# ArduSensor_Shield.net
KiCad netlist of a schematic drawn in EAGLE
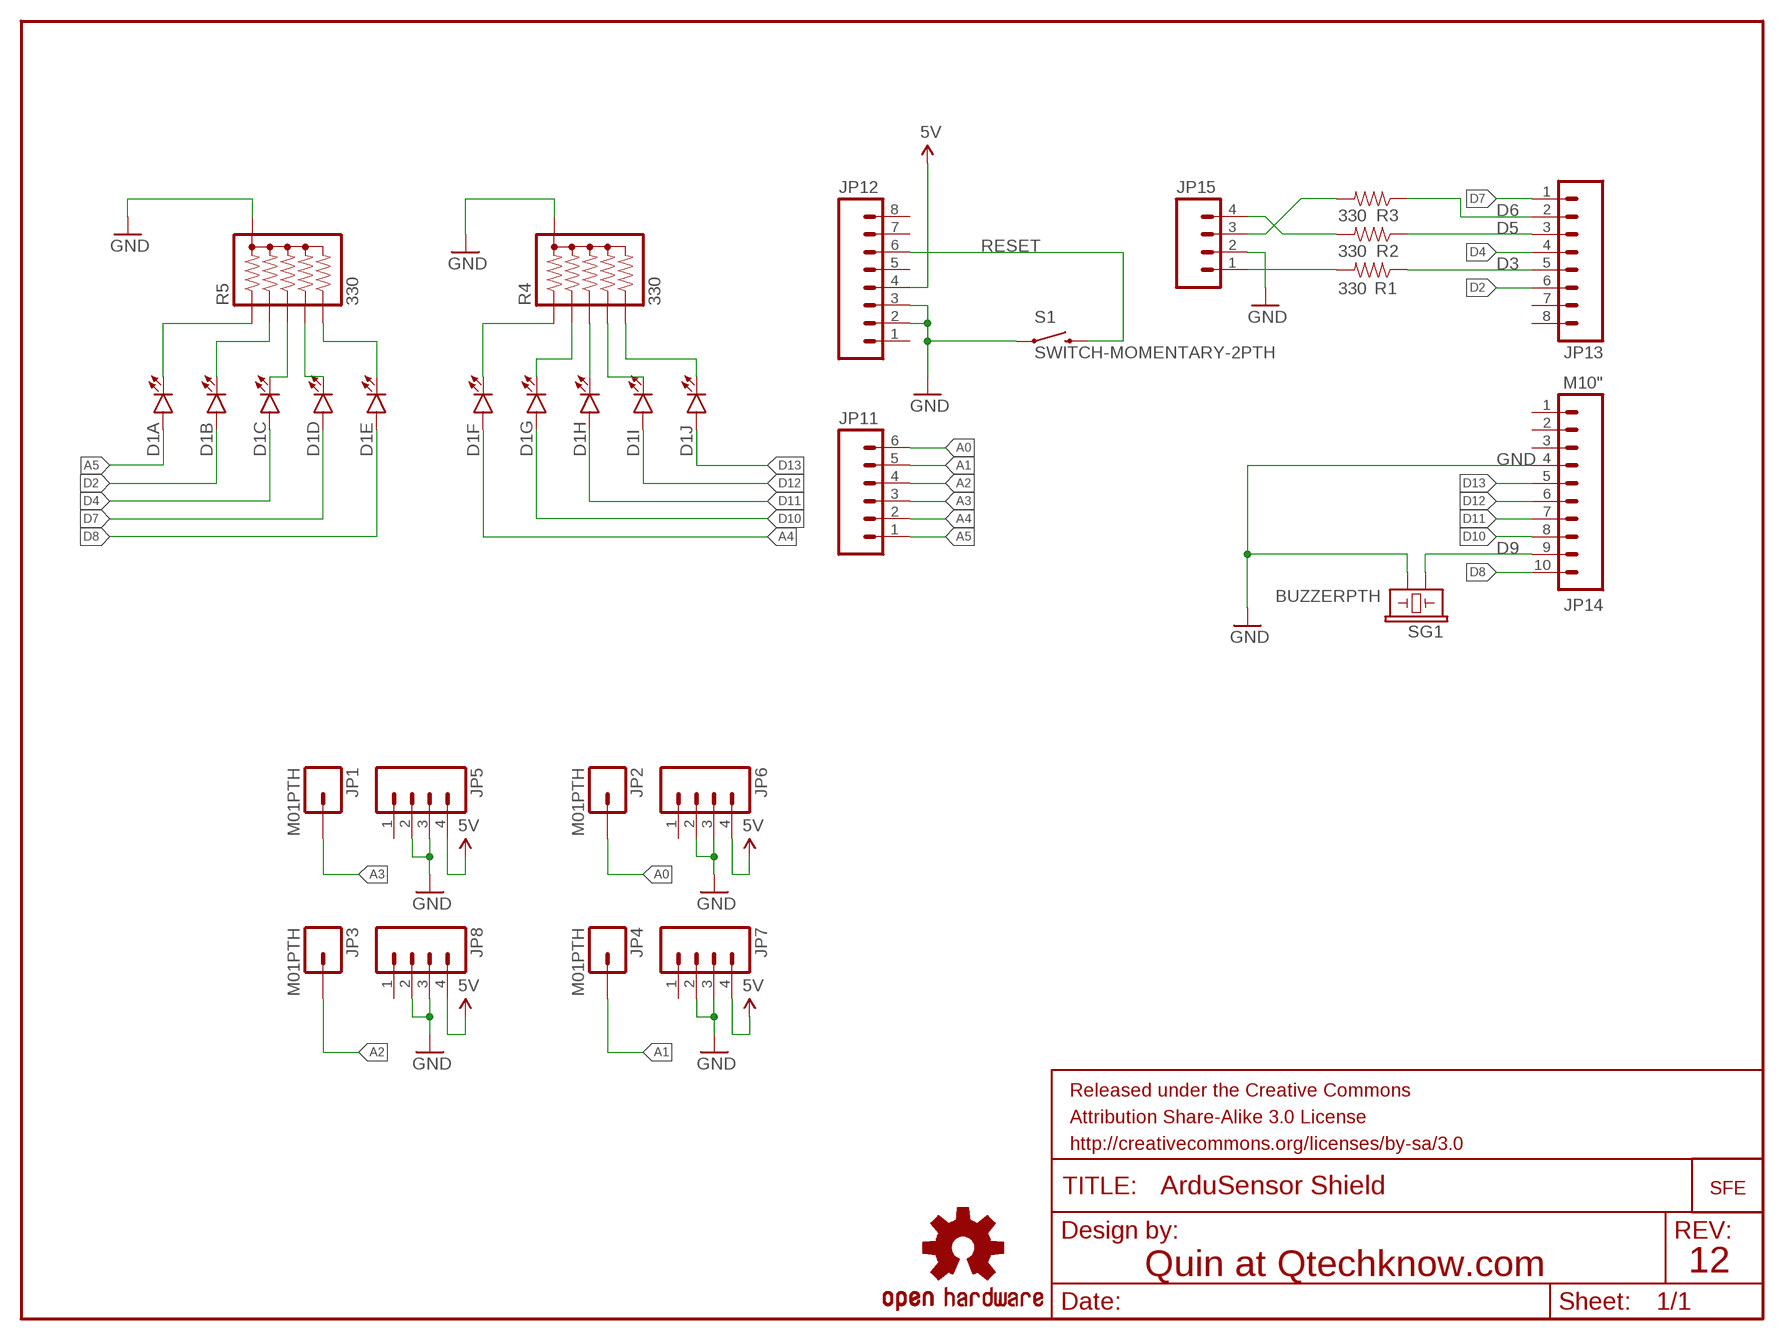
[diagram p0: schematic, sheet 1]

(export (version "E")
  (design (tool "Eeschema 10.0.6"))
  (components
    (comp (ref "D1")
      (value "LED_BARGRAPH_10")
      (footprint "eagle-import:LED_BARGAPH_10")
      (libsource (lib "eagle-import") (part "LED_BARGRAPH_10"))
    )
    (comp (ref "FRAME1")
      (value "FRAME-LETTER")
      (footprint "eagle-import:CREATIVE_COMMONS")
      (libsource (lib "eagle-import") (part "FRAME-LETTER"))
    )
    (comp (ref "JP1")
      (value "M01PTH")
      (footprint "eagle-import:1X01")
      (libsource (lib "eagle-import") (part "M01PTH"))
    )
    (comp (ref "JP2")
      (value "M01PTH")
      (footprint "eagle-import:1X01")
      (libsource (lib "eagle-import") (part "M01PTH"))
    )
    (comp (ref "JP3")
      (value "M01PTH")
      (footprint "eagle-import:1X01")
      (libsource (lib "eagle-import") (part "M01PTH"))
    )
    (comp (ref "JP4")
      (value "M01PTH")
      (footprint "eagle-import:1X01")
      (libsource (lib "eagle-import") (part "M01PTH"))
    )
    (comp (ref "JP5")
      (value "M04PTH")
      (footprint "eagle-import:1X04")
      (libsource (lib "eagle-import") (part "M04PTH"))
    )
    (comp (ref "JP6")
      (value "M04PTH")
      (footprint "eagle-import:1X04")
      (libsource (lib "eagle-import") (part "M04PTH"))
    )
    (comp (ref "JP7")
      (value "M04PTH")
      (footprint "eagle-import:1X04")
      (libsource (lib "eagle-import") (part "M04PTH"))
    )
    (comp (ref "JP8")
      (value "M04PTH")
      (footprint "eagle-import:1X04")
      (libsource (lib "eagle-import") (part "M04PTH"))
    )
    (comp (ref "JP9")
      (value "LOGO-SFENEW")
      (footprint "eagle-import:SFE-NEW-WEBLOGO")
      (libsource (lib "eagle-import") (part "LOGO-SFENEW"))
    )
    (comp (ref "JP11")
      (value "M06SIP")
      (footprint "eagle-import:1X06")
      (libsource (lib "eagle-import") (part "M06SIP"))
    )
    (comp (ref "JP12")
      (value "M081X08")
      (footprint "eagle-import:1X08")
      (libsource (lib "eagle-import") (part "M081X08"))
    )
    (comp (ref "JP13")
      (value "M081X08")
      (footprint "eagle-import:1X08")
      (libsource (lib "eagle-import") (part "M081X08"))
    )
    (comp (ref "JP14")
      (value "M10\"")
      (footprint "eagle-import:1X10")
      (libsource (lib "eagle-import") (part "M10{dblquote}"))
    )
    (comp (ref "JP15")
      (value "M04PTH")
      (footprint "eagle-import:1X04")
      (libsource (lib "eagle-import") (part "M04PTH"))
    )
    (comp (ref "LOGO1")
      (value "OSHW-LOGOM")
      (footprint "eagle-import:OSHW-LOGO-M")
      (libsource (lib "eagle-import") (part "OSHW-LOGOM"))
    )
    (comp (ref "R1")
      (value "330")
      (footprint "eagle-import:1_6W-RES")
      (libsource (lib "eagle-import") (part "RESISTORPTH-1/6W"))
    )
    (comp (ref "R2")
      (value "330")
      (footprint "eagle-import:1_6W-RES")
      (libsource (lib "eagle-import") (part "RESISTORPTH-1/6W"))
    )
    (comp (ref "R3")
      (value "330")
      (footprint "eagle-import:1_6W-RES")
      (libsource (lib "eagle-import") (part "RESISTORPTH-1/6W"))
    )
    (comp (ref "R4")
      (value "330")
      (footprint "eagle-import:RPACK-SIP-PTH-5")
      (libsource (lib "eagle-import") (part "RPACK-BUSSED-SIP-PTH-5"))
    )
    (comp (ref "R5")
      (value "330")
      (footprint "eagle-import:RPACK-SIP-PTH-5")
      (libsource (lib "eagle-import") (part "RPACK-BUSSED-SIP-PTH-5"))
    )
    (comp (ref "S1")
      (value "SWITCH-MOMENTARY-2PTH")
      (footprint "eagle-import:TACTILE-PTH")
      (libsource (lib "eagle-import") (part "SWITCH-MOMENTARY-2PTH"))
    )
    (comp (ref "SG1")
      (value "BUZZERPTH")
      (footprint "eagle-import:BUZZER-12MM")
      (libsource (lib "eagle-import") (part "BUZZERPTH"))
    )
  )
  (nets
    (net (code "1") (name "/D3") (class "Default")
      (node (ref "JP13") (pin "5") (pinfunction "5_5") (pintype "passive"))
      (node (ref "R1") (pin "1") (pinfunction "1_1") (pintype "passive"))
    )
    (net (code "2") (name "/D5") (class "Default")
      (node (ref "JP13") (pin "3") (pinfunction "3_3") (pintype "passive"))
      (node (ref "R2") (pin "1") (pinfunction "1_1") (pintype "passive"))
    )
    (net (code "3") (name "/D6") (class "Default")
      (node (ref "JP13") (pin "2") (pinfunction "2_2") (pintype "passive"))
      (node (ref "R3") (pin "1") (pinfunction "1_1") (pintype "passive"))
    )
    (net (code "4") (name "/D9") (class "Default")
      (node (ref "JP14") (pin "9") (pinfunction "9_9") (pintype "passive"))
      (node (ref "SG1") (pin "+") (pinfunction "1_+") (pintype "passive"))
    )
    (net (code "5") (name "/RESET") (class "Default")
      (node (ref "JP12") (pin "6") (pinfunction "6_6") (pintype "passive"))
      (node (ref "S1") (pin "3") (pinfunction "2_3") (pintype "passive"))
    )
    (net (code "6") (name "5V") (class "Default")
      (node (ref "JP12") (pin "4") (pinfunction "4_4") (pintype "passive"))
      (node (ref "JP5") (pin "4") (pinfunction "4_4") (pintype "passive"))
      (node (ref "JP6") (pin "4") (pinfunction "4_4") (pintype "passive"))
      (node (ref "JP7") (pin "4") (pinfunction "4_4") (pintype "passive"))
      (node (ref "JP8") (pin "4") (pinfunction "4_4") (pintype "passive"))
    )
    (net (code "7") (name "A0") (class "Default")
      (node (ref "JP11") (pin "6") (pinfunction "6_6") (pintype "passive"))
      (node (ref "JP2") (pin "1") (pinfunction "1_1") (pintype "passive"))
    )
    (net (code "8") (name "A1") (class "Default")
      (node (ref "JP11") (pin "5") (pinfunction "5_5") (pintype "passive"))
      (node (ref "JP4") (pin "1") (pinfunction "1_1") (pintype "passive"))
    )
    (net (code "9") (name "A2") (class "Default")
      (node (ref "JP11") (pin "4") (pinfunction "4_4") (pintype "passive"))
      (node (ref "JP3") (pin "1") (pinfunction "1_1") (pintype "passive"))
    )
    (net (code "10") (name "A3") (class "Default")
      (node (ref "JP1") (pin "1") (pinfunction "1_1") (pintype "passive"))
      (node (ref "JP11") (pin "3") (pinfunction "3_3") (pintype "passive"))
    )
    (net (code "11") (name "A4") (class "Default")
      (node (ref "D1") (pin "6") (pinfunction "A_6") (pintype "passive"))
      (node (ref "JP11") (pin "2") (pinfunction "2_2") (pintype "passive"))
    )
    (net (code "12") (name "A5") (class "Default")
      (node (ref "D1") (pin "1") (pinfunction "A_1") (pintype "passive"))
      (node (ref "JP11") (pin "1") (pinfunction "1_1") (pintype "passive"))
    )
    (net (code "13") (name "D2") (class "Default")
      (node (ref "D1") (pin "2") (pinfunction "A_2") (pintype "passive"))
      (node (ref "JP13") (pin "6") (pinfunction "6_6") (pintype "passive"))
    )
    (net (code "14") (name "D4") (class "Default")
      (node (ref "D1") (pin "3") (pinfunction "A_3") (pintype "passive"))
      (node (ref "JP13") (pin "4") (pinfunction "4_4") (pintype "passive"))
    )
    (net (code "15") (name "D7") (class "Default")
      (node (ref "D1") (pin "4") (pinfunction "A_4") (pintype "passive"))
      (node (ref "JP13") (pin "1") (pinfunction "1_1") (pintype "passive"))
    )
    (net (code "16") (name "D8") (class "Default")
      (node (ref "D1") (pin "5") (pinfunction "A_5") (pintype "passive"))
      (node (ref "JP14") (pin "10") (pinfunction "10_10") (pintype "passive"))
    )
    (net (code "17") (name "D10") (class "Default")
      (node (ref "D1") (pin "7") (pinfunction "A_7") (pintype "passive"))
      (node (ref "JP14") (pin "8") (pinfunction "8_8") (pintype "passive"))
    )
    (net (code "18") (name "D11") (class "Default")
      (node (ref "D1") (pin "8") (pinfunction "A_8") (pintype "passive"))
      (node (ref "JP14") (pin "7") (pinfunction "7_7") (pintype "passive"))
    )
    (net (code "19") (name "D12") (class "Default")
      (node (ref "D1") (pin "9") (pinfunction "A_9") (pintype "passive"))
      (node (ref "JP14") (pin "6") (pinfunction "6_6") (pintype "passive"))
    )
    (net (code "20") (name "D13") (class "Default")
      (node (ref "D1") (pin "10") (pinfunction "A_10") (pintype "passive"))
      (node (ref "JP14") (pin "5") (pinfunction "5_5") (pintype "passive"))
    )
    (net (code "21") (name "GND") (class "Default")
      (node (ref "JP12") (pin "2") (pinfunction "2_2") (pintype "passive"))
      (node (ref "JP12") (pin "3") (pinfunction "3_3") (pintype "passive"))
      (node (ref "JP14") (pin "4") (pinfunction "4_4") (pintype "passive"))
      (node (ref "JP15") (pin "2") (pinfunction "2_2") (pintype "passive"))
      (node (ref "JP5") (pin "2") (pinfunction "2_2") (pintype "passive"))
      (node (ref "JP5") (pin "3") (pinfunction "3_3") (pintype "passive"))
      (node (ref "JP6") (pin "2") (pinfunction "2_2") (pintype "passive"))
      (node (ref "JP6") (pin "3") (pinfunction "3_3") (pintype "passive"))
      (node (ref "JP7") (pin "2") (pinfunction "2_2") (pintype "passive"))
      (node (ref "JP7") (pin "3") (pinfunction "3_3") (pintype "passive"))
      (node (ref "JP8") (pin "2") (pinfunction "2_2") (pintype "passive"))
      (node (ref "JP8") (pin "3") (pinfunction "3_3") (pintype "passive"))
      (node (ref "R4") (pin "P$1") (pinfunction "1_P$1") (pintype "passive"))
      (node (ref "R5") (pin "P$1") (pinfunction "1_P$1") (pintype "passive"))
      (node (ref "S1") (pin "1") (pinfunction "1_1") (pintype "passive"))
      (node (ref "SG1") (pin "-") (pinfunction "2_-") (pintype "passive"))
    )
    (net (code "22") (name "Net-(D1A-C)") (class "Default")
      (node (ref "D1") (pin "20") (pinfunction "C_20") (pintype "passive"))
      (node (ref "R5") (pin "P$2") (pinfunction "2_P$2") (pintype "passive"))
    )
    (net (code "23") (name "Net-(D1B-C)") (class "Default")
      (node (ref "D1") (pin "19") (pinfunction "C_19") (pintype "passive"))
      (node (ref "R5") (pin "P$3") (pinfunction "3_P$3") (pintype "passive"))
    )
    (net (code "24") (name "Net-(D1C-C)") (class "Default")
      (node (ref "D1") (pin "18") (pinfunction "C_18") (pintype "passive"))
      (node (ref "R5") (pin "P$4") (pinfunction "4_P$4") (pintype "passive"))
    )
    (net (code "25") (name "Net-(D1D-C)") (class "Default")
      (node (ref "D1") (pin "17") (pinfunction "C_17") (pintype "passive"))
      (node (ref "R5") (pin "P$5") (pinfunction "5_P$5") (pintype "passive"))
    )
    (net (code "26") (name "Net-(D1E-C)") (class "Default")
      (node (ref "D1") (pin "16") (pinfunction "C_16") (pintype "passive"))
      (node (ref "R5") (pin "P$6") (pinfunction "6_P$6") (pintype "passive"))
    )
    (net (code "27") (name "Net-(D1F-C)") (class "Default")
      (node (ref "D1") (pin "15") (pinfunction "C_15") (pintype "passive"))
      (node (ref "R4") (pin "P$2") (pinfunction "2_P$2") (pintype "passive"))
    )
    (net (code "28") (name "Net-(D1G-C)") (class "Default")
      (node (ref "D1") (pin "14") (pinfunction "C_14") (pintype "passive"))
      (node (ref "R4") (pin "P$3") (pinfunction "3_P$3") (pintype "passive"))
    )
    (net (code "29") (name "Net-(D1H-C)") (class "Default")
      (node (ref "D1") (pin "13") (pinfunction "C_13") (pintype "passive"))
      (node (ref "R4") (pin "P$4") (pinfunction "4_P$4") (pintype "passive"))
    )
    (net (code "30") (name "Net-(D1I-C)") (class "Default")
      (node (ref "D1") (pin "12") (pinfunction "C_12") (pintype "passive"))
      (node (ref "R4") (pin "P$5") (pinfunction "5_P$5") (pintype "passive"))
    )
    (net (code "31") (name "Net-(D1J-C)") (class "Default")
      (node (ref "D1") (pin "11") (pinfunction "C_11") (pintype "passive"))
      (node (ref "R4") (pin "P$6") (pinfunction "6_P$6") (pintype "passive"))
    )
    (net (code "32") (name "Net-(JP15-Pad1)") (class "Default")
      (node (ref "JP15") (pin "1") (pinfunction "1_1") (pintype "passive"))
      (node (ref "R1") (pin "2") (pinfunction "2_2") (pintype "passive"))
    )
    (net (code "33") (name "Net-(JP15-Pad3)") (class "Default")
      (node (ref "JP15") (pin "3") (pinfunction "3_3") (pintype "passive"))
      (node (ref "R3") (pin "2") (pinfunction "2_2") (pintype "passive"))
    )
    (net (code "34") (name "Net-(JP15-Pad4)") (class "Default")
      (node (ref "JP15") (pin "4") (pinfunction "4_4") (pintype "passive"))
      (node (ref "R2") (pin "2") (pinfunction "2_2") (pintype "passive"))
    )
    (net (code "35") (name "unconnected-(JP5-Pad1)") (class "Default")
      (node (ref "JP5") (pin "1") (pinfunction "1_1") (pintype "passive"))
    )
    (net (code "36") (name "unconnected-(JP6-Pad1)") (class "Default")
      (node (ref "JP6") (pin "1") (pinfunction "1_1") (pintype "passive"))
    )
    (net (code "37") (name "unconnected-(JP7-Pad1)") (class "Default")
      (node (ref "JP7") (pin "1") (pinfunction "1_1") (pintype "passive"))
    )
    (net (code "38") (name "unconnected-(JP8-Pad1)") (class "Default")
      (node (ref "JP8") (pin "1") (pinfunction "1_1") (pintype "passive"))
    )
    (net (code "39") (name "unconnected-(JP12-Pad1)") (class "Default")
      (node (ref "JP12") (pin "1") (pinfunction "1_1") (pintype "passive"))
    )
    (net (code "40") (name "unconnected-(JP12-Pad5)") (class "Default")
      (node (ref "JP12") (pin "5") (pinfunction "5_5") (pintype "passive"))
    )
    (net (code "41") (name "unconnected-(JP12-Pad7)") (class "Default")
      (node (ref "JP12") (pin "7") (pinfunction "7_7") (pintype "passive"))
    )
    (net (code "42") (name "unconnected-(JP12-Pad8)") (class "Default")
      (node (ref "JP12") (pin "8") (pinfunction "8_8") (pintype "passive"))
    )
    (net (code "43") (name "unconnected-(JP13-Pad7)") (class "Default")
      (node (ref "JP13") (pin "7") (pinfunction "7_7") (pintype "passive"))
    )
    (net (code "44") (name "unconnected-(JP13-Pad8)") (class "Default")
      (node (ref "JP13") (pin "8") (pinfunction "8_8") (pintype "passive"))
    )
    (net (code "45") (name "unconnected-(JP14-Pad1)") (class "Default")
      (node (ref "JP14") (pin "1") (pinfunction "1_1") (pintype "passive"))
    )
    (net (code "46") (name "unconnected-(JP14-Pad2)") (class "Default")
      (node (ref "JP14") (pin "2") (pinfunction "2_2") (pintype "passive"))
    )
    (net (code "47") (name "unconnected-(JP14-Pad3)") (class "Default")
      (node (ref "JP14") (pin "3") (pinfunction "3_3") (pintype "passive"))
    )
  )
)
